# NT_SolarModule.net
KiCad netlist of a schematic drawn in EAGLE
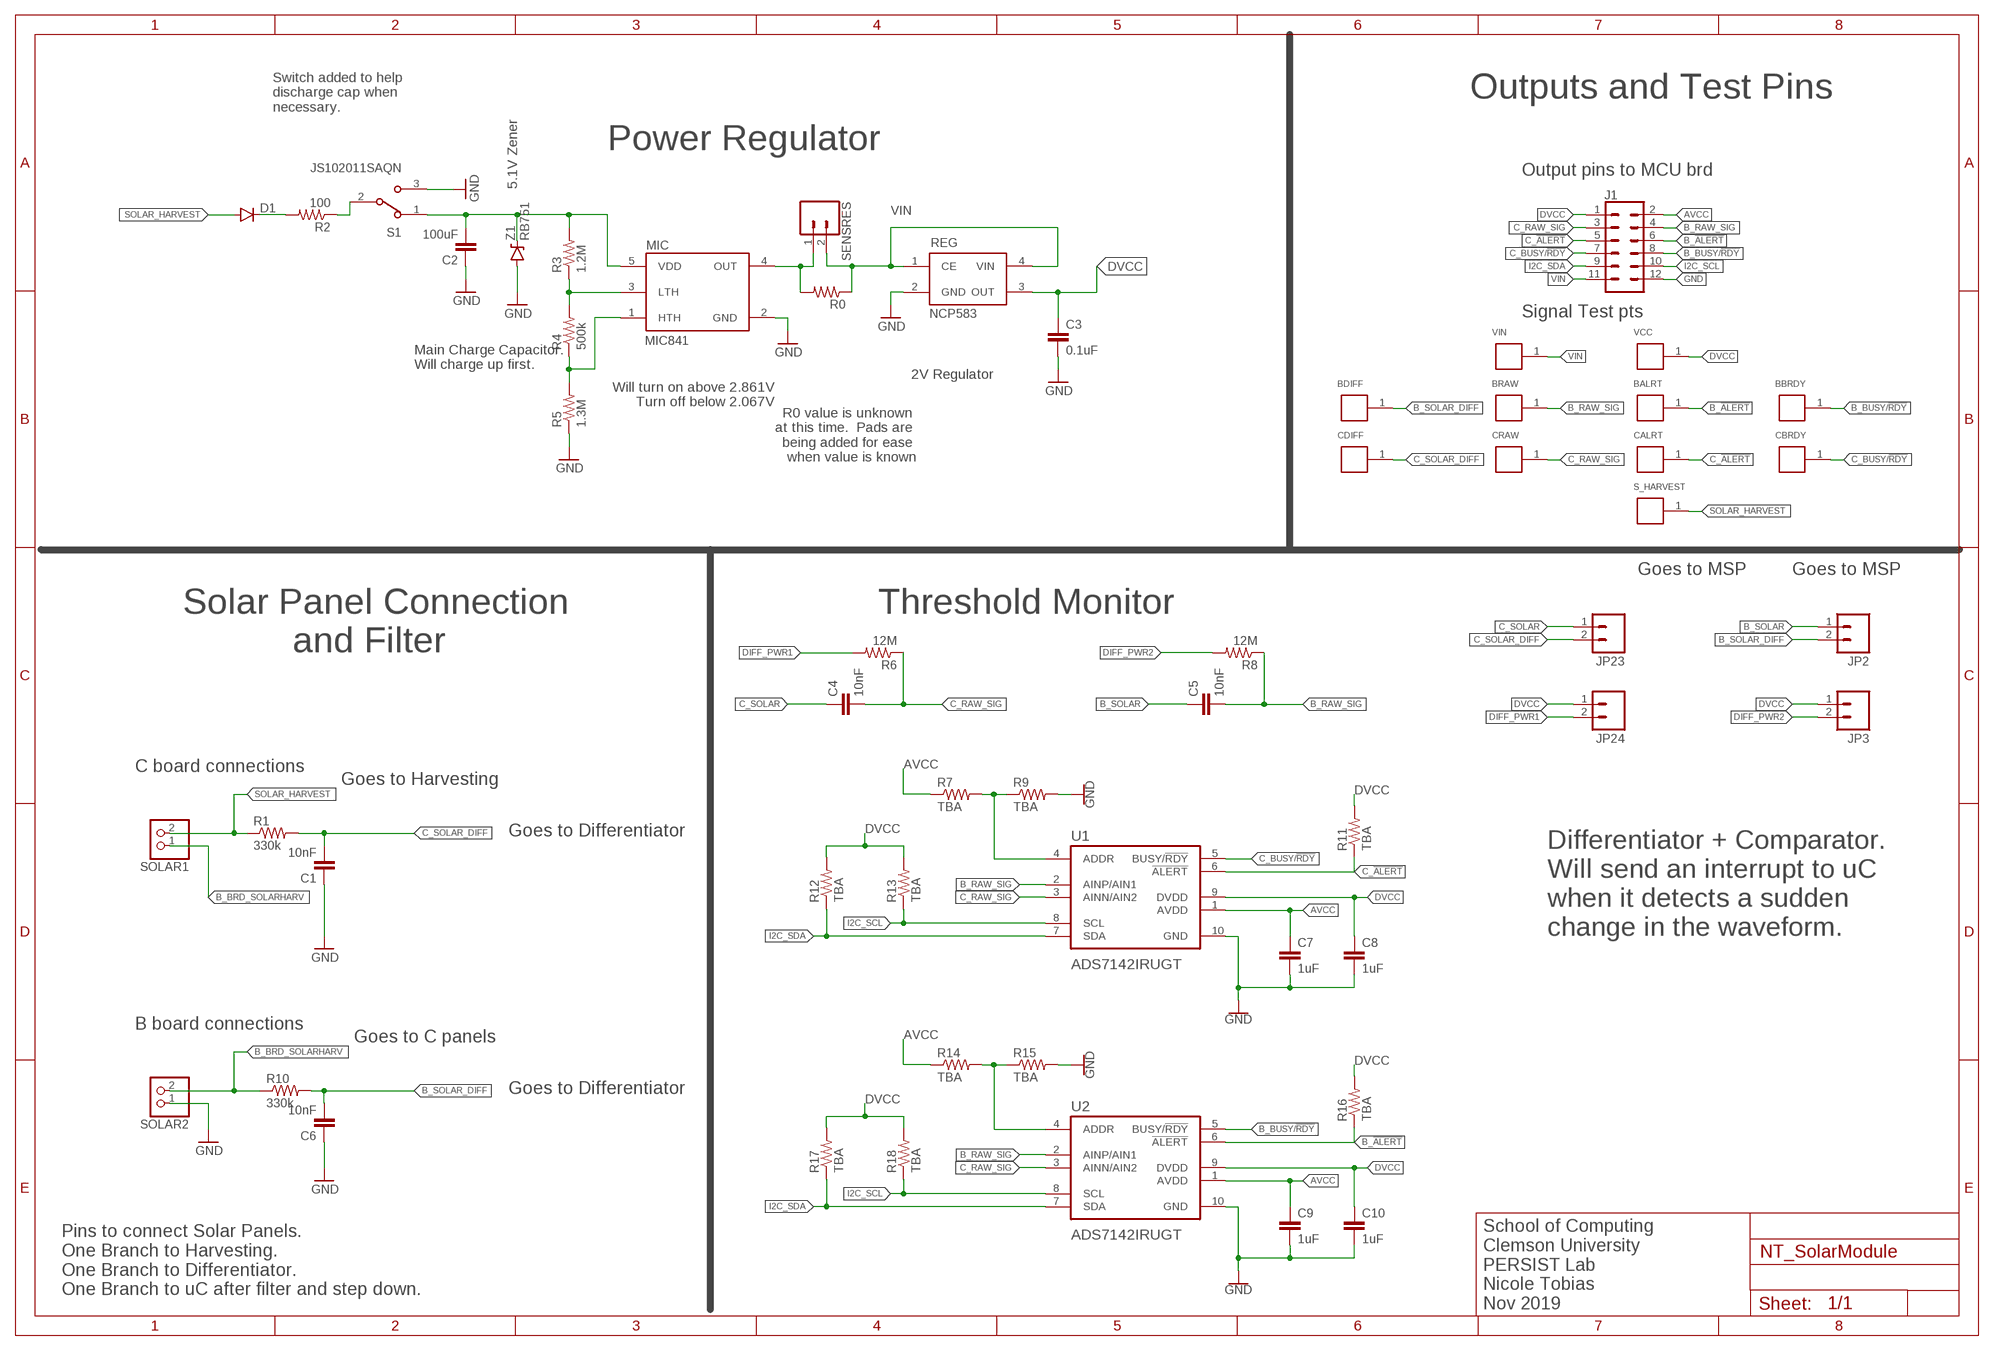
[diagram p0: schematic, sheet 1]

(export (version "E")
  (design (tool "Eeschema 10.0.6"))
  (components
    (comp (ref "BALRT")
      (value "RCU-0C")
      (footprint "eagle-import:TE_RCU-0C")
      (fields
        (field (name "COMMENT") "RCU-0C _1625854-3_")
        (field (name "MF") "TE Connectivity")
        (field (name "TOLERANCE") "0%")
      )
      (libsource (lib "eagle-import") (part "RCU-0C"))
    )
    (comp (ref "BBRDY")
      (value "RCU-0C")
      (footprint "eagle-import:TE_RCU-0C")
      (fields
        (field (name "COMMENT") "RCU-0C _1625854-3_")
        (field (name "MF") "TE Connectivity")
        (field (name "TOLERANCE") "0%")
      )
      (libsource (lib "eagle-import") (part "RCU-0C"))
    )
    (comp (ref "BDIFF")
      (value "RCU-0C")
      (footprint "eagle-import:TE_RCU-0C")
      (fields
        (field (name "COMMENT") "RCU-0C _1625854-3_")
        (field (name "MF") "TE Connectivity")
        (field (name "TOLERANCE") "0%")
      )
      (libsource (lib "eagle-import") (part "RCU-0C"))
    )
    (comp (ref "BRAW")
      (value "RCU-0C")
      (footprint "eagle-import:TE_RCU-0C")
      (fields
        (field (name "COMMENT") "RCU-0C _1625854-3_")
        (field (name "MF") "TE Connectivity")
        (field (name "TOLERANCE") "0%")
      )
      (libsource (lib "eagle-import") (part "RCU-0C"))
    )
    (comp (ref "C1")
      (value "10nF")
      (footprint "eagle-import:0603-CAP")
      (libsource (lib "eagle-import") (part "CAP0603-CAP"))
    )
    (comp (ref "C2")
      (value "100uF")
      (footprint "eagle-import:0603-CAP")
      (libsource (lib "eagle-import") (part "CAP0603-CAP"))
    )
    (comp (ref "C3")
      (value "0.1uF")
      (footprint "eagle-import:0603-CAP")
      (libsource (lib "eagle-import") (part "CAP0603-CAP"))
    )
    (comp (ref "C4")
      (value "10nF")
      (footprint "eagle-import:0603-CAP")
      (libsource (lib "eagle-import") (part "CAP0603-CAP"))
    )
    (comp (ref "C5")
      (value "10nF")
      (footprint "eagle-import:0603-CAP")
      (libsource (lib "eagle-import") (part "CAP0603-CAP"))
    )
    (comp (ref "C6")
      (value "10nF")
      (footprint "eagle-import:0603-CAP")
      (libsource (lib "eagle-import") (part "CAP0603-CAP"))
    )
    (comp (ref "C7")
      (value "1uF")
      (footprint "eagle-import:0603-CAP")
      (libsource (lib "eagle-import") (part "CAP0603-CAP"))
    )
    (comp (ref "C8")
      (value "1uF")
      (footprint "eagle-import:0603-CAP")
      (libsource (lib "eagle-import") (part "CAP0603-CAP"))
    )
    (comp (ref "C9")
      (value "1uF")
      (footprint "eagle-import:0603-CAP")
      (libsource (lib "eagle-import") (part "CAP0603-CAP"))
    )
    (comp (ref "C10")
      (value "1uF")
      (footprint "eagle-import:0603-CAP")
      (libsource (lib "eagle-import") (part "CAP0603-CAP"))
    )
    (comp (ref "CALRT")
      (value "RCU-0C")
      (footprint "eagle-import:TE_RCU-0C")
      (fields
        (field (name "COMMENT") "RCU-0C _1625854-3_")
        (field (name "MF") "TE Connectivity")
        (field (name "TOLERANCE") "0%")
      )
      (libsource (lib "eagle-import") (part "RCU-0C"))
    )
    (comp (ref "CBRDY")
      (value "RCU-0C")
      (footprint "eagle-import:TE_RCU-0C")
      (fields
        (field (name "COMMENT") "RCU-0C _1625854-3_")
        (field (name "MF") "TE Connectivity")
        (field (name "TOLERANCE") "0%")
      )
      (libsource (lib "eagle-import") (part "RCU-0C"))
    )
    (comp (ref "CDIFF")
      (value "RCU-0C")
      (footprint "eagle-import:TE_RCU-0C")
      (fields
        (field (name "COMMENT") "RCU-0C _1625854-3_")
        (field (name "MF") "TE Connectivity")
        (field (name "TOLERANCE") "0%")
      )
      (libsource (lib "eagle-import") (part "RCU-0C"))
    )
    (comp (ref "CRAW")
      (value "RCU-0C")
      (footprint "eagle-import:TE_RCU-0C")
      (fields
        (field (name "COMMENT") "RCU-0C _1625854-3_")
        (field (name "MF") "TE Connectivity")
        (field (name "TOLERANCE") "0%")
      )
      (libsource (lib "eagle-import") (part "RCU-0C"))
    )
    (comp (ref "D1")
      (value "DIODESOD523")
      (footprint "eagle-import:SOD523")
      (libsource (lib "eagle-import") (part "DIODESOD523"))
    )
    (comp (ref "J1")
      (value "2X6 FEMALE")
      (footprint "eagle-import:2X6")
      (libsource (lib "eagle-import") (part "CONN_06X2PTH_FEMALE"))
    )
    (comp (ref "JP2")
      (value "M02")
      (footprint "eagle-import:1X02-1.27MM")
      (libsource (lib "eagle-import") (part "M02"))
    )
    (comp (ref "JP3")
      (value "M02")
      (footprint "eagle-import:1X02-1.27MM")
      (libsource (lib "eagle-import") (part "M02"))
    )
    (comp (ref "JP23")
      (value "M02")
      (footprint "eagle-import:1X02-1.27MM")
      (libsource (lib "eagle-import") (part "M02"))
    )
    (comp (ref "JP24")
      (value "M02")
      (footprint "eagle-import:1X02-1.27MM")
      (libsource (lib "eagle-import") (part "M02"))
    )
    (comp (ref "MIC")
      (value "MIC841")
      (footprint "eagle-import:SC70-5")
      (libsource (lib "eagle-import") (part "MIC841"))
    )
    (comp (ref "R0")
      (value "RESISTOR0603")
      (footprint "eagle-import:0603-RES")
      (libsource (lib "eagle-import") (part "RESISTOR0603"))
    )
    (comp (ref "R1")
      (value "330k")
      (footprint "eagle-import:0603-RES")
      (libsource (lib "eagle-import") (part "RESISTOR0603"))
    )
    (comp (ref "R2")
      (value "100")
      (footprint "eagle-import:0603-RES")
      (libsource (lib "eagle-import") (part "RESISTOR0603"))
    )
    (comp (ref "R3")
      (value "1.2M")
      (footprint "eagle-import:0603-RES")
      (libsource (lib "eagle-import") (part "RESISTOR0603"))
    )
    (comp (ref "R4")
      (value "500k")
      (footprint "eagle-import:0603-RES")
      (libsource (lib "eagle-import") (part "RESISTOR0603"))
    )
    (comp (ref "R5")
      (value "1.3M")
      (footprint "eagle-import:0603-RES")
      (libsource (lib "eagle-import") (part "RESISTOR0603"))
    )
    (comp (ref "R6")
      (value "12M")
      (footprint "eagle-import:0603-RES")
      (libsource (lib "eagle-import") (part "RESISTOR0603"))
    )
    (comp (ref "R7")
      (value "TBA")
      (footprint "eagle-import:0603-RES")
      (libsource (lib "eagle-import") (part "RESISTOR0603"))
    )
    (comp (ref "R8")
      (value "12M")
      (footprint "eagle-import:0603-RES")
      (libsource (lib "eagle-import") (part "RESISTOR0603"))
    )
    (comp (ref "R9")
      (value "TBA")
      (footprint "eagle-import:0603-RES")
      (libsource (lib "eagle-import") (part "RESISTOR0603"))
    )
    (comp (ref "R10")
      (value "330k")
      (footprint "eagle-import:0603-RES")
      (libsource (lib "eagle-import") (part "RESISTOR0603"))
    )
    (comp (ref "R11")
      (value "TBA")
      (footprint "eagle-import:0603-RES")
      (libsource (lib "eagle-import") (part "RESISTOR0603"))
    )
    (comp (ref "R12")
      (value "TBA")
      (footprint "eagle-import:0603-RES")
      (libsource (lib "eagle-import") (part "RESISTOR0603"))
    )
    (comp (ref "R13")
      (value "TBA")
      (footprint "eagle-import:0603-RES")
      (libsource (lib "eagle-import") (part "RESISTOR0603"))
    )
    (comp (ref "R14")
      (value "TBA")
      (footprint "eagle-import:0603-RES")
      (libsource (lib "eagle-import") (part "RESISTOR0603"))
    )
    (comp (ref "R15")
      (value "TBA")
      (footprint "eagle-import:0603-RES")
      (libsource (lib "eagle-import") (part "RESISTOR0603"))
    )
    (comp (ref "R16")
      (value "TBA")
      (footprint "eagle-import:0603-RES")
      (libsource (lib "eagle-import") (part "RESISTOR0603"))
    )
    (comp (ref "R17")
      (value "TBA")
      (footprint "eagle-import:0603-RES")
      (libsource (lib "eagle-import") (part "RESISTOR0603"))
    )
    (comp (ref "R18")
      (value "TBA")
      (footprint "eagle-import:0603-RES")
      (libsource (lib "eagle-import") (part "RESISTOR0603"))
    )
    (comp (ref "REG")
      (value "NCP583")
      (footprint "eagle-import:SC82-AB_1PRIMARY")
      (libsource (lib "eagle-import") (part "NCP583"))
    )
    (comp (ref "S1")
      (value "JS102011SAQN")
      (footprint "eagle-import:SW_JS102011SAQN")
      (fields (field (name "MF") "C&K Components"))
      (libsource (lib "eagle-import") (part "JS102011SAQN"))
    )
    (comp (ref "SENSRES")
      (value "CONN_02")
      (footprint "eagle-import:1X02")
      (libsource (lib "eagle-import") (part "CONN_02"))
    )
    (comp (ref "SOLAR1")
      (value "PINHD-1X2")
      (footprint "eagle-import:1X02")
      (libsource (lib "eagle-import") (part "PINHD-1X2"))
    )
    (comp (ref "SOLAR2")
      (value "PINHD-1X2")
      (footprint "eagle-import:1X02")
      (libsource (lib "eagle-import") (part "PINHD-1X2"))
    )
    (comp (ref "S_HARVEST")
      (value "RCU-0C")
      (footprint "eagle-import:TE_RCU-0C")
      (fields
        (field (name "COMMENT") "RCU-0C _1625854-3_")
        (field (name "MF") "TE Connectivity")
        (field (name "TOLERANCE") "0%")
      )
      (libsource (lib "eagle-import") (part "RCU-0C"))
    )
    (comp (ref "U1")
      (value "ADS7142IRUGT")
      (footprint "eagle-import:QFN50P200X150X40-10N")
      (fields (field (name "MF") "Texas Instruments"))
      (libsource (lib "eagle-import") (part "ADS7142IRUGT"))
    )
    (comp (ref "U2")
      (value "ADS7142IRUGT")
      (footprint "eagle-import:QFN50P200X150X40-10N")
      (fields (field (name "MF") "Texas Instruments"))
      (libsource (lib "eagle-import") (part "ADS7142IRUGT"))
    )
    (comp (ref "VCC")
      (value "RCU-0C")
      (footprint "eagle-import:TE_RCU-0C")
      (fields
        (field (name "COMMENT") "RCU-0C _1625854-3_")
        (field (name "MF") "TE Connectivity")
        (field (name "TOLERANCE") "0%")
      )
      (libsource (lib "eagle-import") (part "RCU-0C"))
    )
    (comp (ref "VIN")
      (value "RCU-0C")
      (footprint "eagle-import:TE_RCU-0C")
      (fields
        (field (name "COMMENT") "RCU-0C _1625854-3_")
        (field (name "MF") "TE Connectivity")
        (field (name "TOLERANCE") "0%")
      )
      (libsource (lib "eagle-import") (part "RCU-0C"))
    )
    (comp (ref "Z1")
      (value "RB751")
      (footprint "eagle-import:SOD-523")
      (libsource (lib "eagle-import") (part "DIODE-ZENER"))
    )
  )
  (nets
    (net (code "1") (name "/B_BUSY{slash}~{RDY}") (class "Default")
      (node (ref "BBRDY") (pin "1") (pinfunction "1_1") (pintype "passive"))
      (node (ref "J1") (pin "8") (pinfunction "8_8") (pintype "passive"))
      (node (ref "U2") (pin "5") (pinfunction "BUSY/~{RDY}_5") (pintype "bidirectional"))
    )
    (net (code "2") (name "/B_~{ALERT}") (class "Default")
      (node (ref "BALRT") (pin "1") (pinfunction "1_1") (pintype "passive"))
      (node (ref "J1") (pin "6") (pinfunction "6_6") (pintype "passive"))
      (node (ref "R16") (pin "1") (pinfunction "1_1") (pintype "passive"))
      (node (ref "U2") (pin "6") (pinfunction "~{ALERT}_6") (pintype "output"))
    )
    (net (code "3") (name "/C_BUSY{slash}~{RDY}") (class "Default")
      (node (ref "CBRDY") (pin "1") (pinfunction "1_1") (pintype "passive"))
      (node (ref "J1") (pin "7") (pinfunction "7_7") (pintype "passive"))
      (node (ref "U1") (pin "5") (pinfunction "BUSY/~{RDY}_5") (pintype "bidirectional"))
    )
    (net (code "4") (name "/C_~{ALERT}") (class "Default")
      (node (ref "CALRT") (pin "1") (pinfunction "1_1") (pintype "passive"))
      (node (ref "J1") (pin "5") (pinfunction "5_5") (pintype "passive"))
      (node (ref "R11") (pin "1") (pinfunction "1_1") (pintype "passive"))
      (node (ref "U1") (pin "6") (pinfunction "~{ALERT}_6") (pintype "output"))
    )
    (net (code "5") (name "AVCC") (class "Default")
      (node (ref "C7") (pin "1") (pinfunction "1_1") (pintype "passive"))
      (node (ref "C9") (pin "1") (pinfunction "1_1") (pintype "passive"))
      (node (ref "J1") (pin "2") (pinfunction "2_2") (pintype "passive"))
      (node (ref "R14") (pin "1") (pinfunction "1_1") (pintype "passive"))
      (node (ref "R7") (pin "1") (pinfunction "1_1") (pintype "passive"))
      (node (ref "U1") (pin "1") (pinfunction "AVDD_1") (pintype "power_in"))
      (node (ref "U2") (pin "1") (pinfunction "AVDD_1") (pintype "power_in"))
    )
    (net (code "6") (name "B_BRD_SOLARHARV") (class "Default")
      (node (ref "R10") (pin "1") (pinfunction "1_1") (pintype "passive"))
      (node (ref "SOLAR1") (pin "1") (pinfunction "1_1") (pintype "passive"))
      (node (ref "SOLAR2") (pin "2") (pinfunction "2_2") (pintype "passive"))
    )
    (net (code "7") (name "B_RAW_SIG") (class "Default")
      (node (ref "BRAW") (pin "1") (pinfunction "1_1") (pintype "passive"))
      (node (ref "C5") (pin "2") (pinfunction "2_2") (pintype "passive"))
      (node (ref "J1") (pin "4") (pinfunction "4_4") (pintype "passive"))
      (node (ref "R8") (pin "1") (pinfunction "1_1") (pintype "passive"))
      (node (ref "U1") (pin "2") (pinfunction "AINP/AIN1_2") (pintype "input"))
      (node (ref "U2") (pin "2") (pinfunction "AINP/AIN1_2") (pintype "input"))
    )
    (net (code "8") (name "B_SOLAR") (class "Default")
      (node (ref "C5") (pin "1") (pinfunction "1_1") (pintype "passive"))
      (node (ref "JP2") (pin "1") (pinfunction "1_1") (pintype "passive"))
    )
    (net (code "9") (name "B_SOLAR_DIFF") (class "Default")
      (node (ref "BDIFF") (pin "1") (pinfunction "1_1") (pintype "passive"))
      (node (ref "C6") (pin "2") (pinfunction "2_2") (pintype "passive"))
      (node (ref "JP2") (pin "2") (pinfunction "2_2") (pintype "passive"))
      (node (ref "R10") (pin "2") (pinfunction "2_2") (pintype "passive"))
    )
    (net (code "10") (name "C_RAW_SIG") (class "Default")
      (node (ref "C4") (pin "2") (pinfunction "2_2") (pintype "passive"))
      (node (ref "CRAW") (pin "1") (pinfunction "1_1") (pintype "passive"))
      (node (ref "J1") (pin "3") (pinfunction "3_3") (pintype "passive"))
      (node (ref "R6") (pin "1") (pinfunction "1_1") (pintype "passive"))
      (node (ref "U1") (pin "3") (pinfunction "AINN/AIN2_3") (pintype "input"))
      (node (ref "U2") (pin "3") (pinfunction "AINN/AIN2_3") (pintype "input"))
    )
    (net (code "11") (name "C_SOLAR") (class "Default")
      (node (ref "C4") (pin "1") (pinfunction "1_1") (pintype "passive"))
      (node (ref "JP23") (pin "1") (pinfunction "1_1") (pintype "passive"))
    )
    (net (code "12") (name "C_SOLAR_DIFF") (class "Default")
      (node (ref "C1") (pin "2") (pinfunction "2_2") (pintype "passive"))
      (node (ref "CDIFF") (pin "1") (pinfunction "1_1") (pintype "passive"))
      (node (ref "JP23") (pin "2") (pinfunction "2_2") (pintype "passive"))
      (node (ref "R1") (pin "2") (pinfunction "2_2") (pintype "passive"))
    )
    (net (code "13") (name "DIFF_PWR1") (class "Default")
      (node (ref "JP24") (pin "2") (pinfunction "2_2") (pintype "passive"))
      (node (ref "R6") (pin "2") (pinfunction "2_2") (pintype "passive"))
    )
    (net (code "14") (name "DIFF_PWR2") (class "Default")
      (node (ref "JP3") (pin "2") (pinfunction "2_2") (pintype "passive"))
      (node (ref "R8") (pin "2") (pinfunction "2_2") (pintype "passive"))
    )
    (net (code "15") (name "DVCC") (class "Default")
      (node (ref "C10") (pin "1") (pinfunction "1_1") (pintype "passive"))
      (node (ref "C3") (pin "1") (pinfunction "1_1") (pintype "passive"))
      (node (ref "C8") (pin "1") (pinfunction "1_1") (pintype "passive"))
      (node (ref "J1") (pin "1") (pinfunction "1_1") (pintype "passive"))
      (node (ref "JP24") (pin "1") (pinfunction "1_1") (pintype "passive"))
      (node (ref "JP3") (pin "1") (pinfunction "1_1") (pintype "passive"))
      (node (ref "R11") (pin "2") (pinfunction "2_2") (pintype "passive"))
      (node (ref "R12") (pin "2") (pinfunction "2_2") (pintype "passive"))
      (node (ref "R13") (pin "2") (pinfunction "2_2") (pintype "passive"))
      (node (ref "R16") (pin "2") (pinfunction "2_2") (pintype "passive"))
      (node (ref "R17") (pin "2") (pinfunction "2_2") (pintype "passive"))
      (node (ref "R18") (pin "2") (pinfunction "2_2") (pintype "passive"))
      (node (ref "REG") (pin "3") (pinfunction "OUT_3") (pintype "bidirectional"))
      (node (ref "U1") (pin "9") (pinfunction "DVDD_9") (pintype "power_in"))
      (node (ref "U2") (pin "9") (pinfunction "DVDD_9") (pintype "power_in"))
      (node (ref "VCC") (pin "1") (pinfunction "1_1") (pintype "passive"))
    )
    (net (code "16") (name "GND") (class "Default")
      (node (ref "C1") (pin "1") (pinfunction "1_1") (pintype "passive"))
      (node (ref "C10") (pin "2") (pinfunction "2_2") (pintype "passive"))
      (node (ref "C2") (pin "1") (pinfunction "1_1") (pintype "passive"))
      (node (ref "C3") (pin "2") (pinfunction "2_2") (pintype "passive"))
      (node (ref "C6") (pin "1") (pinfunction "1_1") (pintype "passive"))
      (node (ref "C7") (pin "2") (pinfunction "2_2") (pintype "passive"))
      (node (ref "C8") (pin "2") (pinfunction "2_2") (pintype "passive"))
      (node (ref "C9") (pin "2") (pinfunction "2_2") (pintype "passive"))
      (node (ref "J1") (pin "12") (pinfunction "12_12") (pintype "passive"))
      (node (ref "MIC") (pin "2") (pinfunction "GND_2") (pintype "bidirectional"))
      (node (ref "R15") (pin "2") (pinfunction "2_2") (pintype "passive"))
      (node (ref "R5") (pin "1") (pinfunction "1_1") (pintype "passive"))
      (node (ref "R9") (pin "2") (pinfunction "2_2") (pintype "passive"))
      (node (ref "REG") (pin "2") (pinfunction "GND_2") (pintype "bidirectional"))
      (node (ref "S1") (pin "3") (pinfunction "3_3") (pintype "passive"))
      (node (ref "SOLAR2") (pin "1") (pinfunction "1_1") (pintype "passive"))
      (node (ref "U1") (pin "10") (pinfunction "GND_10") (pintype "power_in"))
      (node (ref "U2") (pin "10") (pinfunction "GND_10") (pintype "power_in"))
      (node (ref "Z1") (pin "ANODE") (pinfunction "A_ANODE") (pintype "passive"))
    )
    (net (code "17") (name "I2C_SCL") (class "Default")
      (node (ref "J1") (pin "10") (pinfunction "10_10") (pintype "passive"))
      (node (ref "R13") (pin "1") (pinfunction "1_1") (pintype "passive"))
      (node (ref "R18") (pin "1") (pinfunction "1_1") (pintype "passive"))
      (node (ref "U1") (pin "8") (pinfunction "SCL_8") (pintype "input"))
      (node (ref "U2") (pin "8") (pinfunction "SCL_8") (pintype "input"))
    )
    (net (code "18") (name "I2C_SDA") (class "Default")
      (node (ref "J1") (pin "9") (pinfunction "9_9") (pintype "passive"))
      (node (ref "R12") (pin "1") (pinfunction "1_1") (pintype "passive"))
      (node (ref "R17") (pin "1") (pinfunction "1_1") (pintype "passive"))
      (node (ref "U1") (pin "7") (pinfunction "SDA_7") (pintype "bidirectional"))
      (node (ref "U2") (pin "7") (pinfunction "SDA_7") (pintype "bidirectional"))
    )
    (net (code "19") (name "Net-(D1-PadC)") (class "Default")
      (node (ref "D1") (pin "C") (pinfunction "C_C") (pintype "passive"))
      (node (ref "R2") (pin "2") (pinfunction "2_2") (pintype "passive"))
    )
    (net (code "20") (name "Net-(MIC-HTH)") (class "Default")
      (node (ref "MIC") (pin "1") (pinfunction "HTH_1") (pintype "bidirectional"))
      (node (ref "R4") (pin "1") (pinfunction "1_1") (pintype "passive"))
      (node (ref "R5") (pin "2") (pinfunction "2_2") (pintype "passive"))
    )
    (net (code "21") (name "Net-(MIC-LTH)") (class "Default")
      (node (ref "MIC") (pin "3") (pinfunction "LTH_3") (pintype "bidirectional"))
      (node (ref "R3") (pin "1") (pinfunction "1_1") (pintype "passive"))
      (node (ref "R4") (pin "2") (pinfunction "2_2") (pintype "passive"))
    )
    (net (code "22") (name "Net-(MIC-OUT)") (class "Default")
      (node (ref "MIC") (pin "4") (pinfunction "OUT_4") (pintype "bidirectional"))
      (node (ref "R0") (pin "2") (pinfunction "2_2") (pintype "passive"))
      (node (ref "SENSRES") (pin "1") (pinfunction "1_1") (pintype "passive"))
    )
    (net (code "23") (name "Net-(MIC-VDD)") (class "Default")
      (node (ref "C2") (pin "2") (pinfunction "2_2") (pintype "passive"))
      (node (ref "MIC") (pin "5") (pinfunction "VDD_5") (pintype "bidirectional"))
      (node (ref "R3") (pin "2") (pinfunction "2_2") (pintype "passive"))
      (node (ref "S1") (pin "1") (pinfunction "1_1") (pintype "passive"))
      (node (ref "Z1") (pin "CATHODE") (pinfunction "C_CATHODE") (pintype "passive"))
    )
    (net (code "24") (name "Net-(R2-Pad1)") (class "Default")
      (node (ref "R2") (pin "1") (pinfunction "1_1") (pintype "passive"))
      (node (ref "S1") (pin "2") (pinfunction "2_2") (pintype "passive"))
    )
    (net (code "25") (name "Net-(U1-ADDR)") (class "Default")
      (node (ref "R7") (pin "2") (pinfunction "2_2") (pintype "passive"))
      (node (ref "R9") (pin "1") (pinfunction "1_1") (pintype "passive"))
      (node (ref "U1") (pin "4") (pinfunction "ADDR_4") (pintype "input"))
    )
    (net (code "26") (name "Net-(U2-ADDR)") (class "Default")
      (node (ref "R14") (pin "2") (pinfunction "2_2") (pintype "passive"))
      (node (ref "R15") (pin "1") (pinfunction "1_1") (pintype "passive"))
      (node (ref "U2") (pin "4") (pinfunction "ADDR_4") (pintype "input"))
    )
    (net (code "27") (name "SOLAR_HARVEST") (class "Default")
      (node (ref "D1") (pin "A") (pinfunction "A_A") (pintype "passive"))
      (node (ref "R1") (pin "1") (pinfunction "1_1") (pintype "passive"))
      (node (ref "SOLAR1") (pin "2") (pinfunction "2_2") (pintype "passive"))
      (node (ref "S_HARVEST") (pin "1") (pinfunction "1_1") (pintype "passive"))
    )
    (net (code "28") (name "VIN") (class "Default")
      (node (ref "J1") (pin "11") (pinfunction "11_11") (pintype "passive"))
      (node (ref "R0") (pin "1") (pinfunction "1_1") (pintype "passive"))
      (node (ref "REG") (pin "1") (pinfunction "CE_1") (pintype "bidirectional"))
      (node (ref "REG") (pin "4") (pinfunction "VIN_4") (pintype "bidirectional"))
      (node (ref "SENSRES") (pin "2") (pinfunction "2_2") (pintype "passive"))
      (node (ref "VIN") (pin "1") (pinfunction "1_1") (pintype "passive"))
    )
  )
)
